# mother_card_1.net
KiCad netlist of a schematic drawn in EAGLE
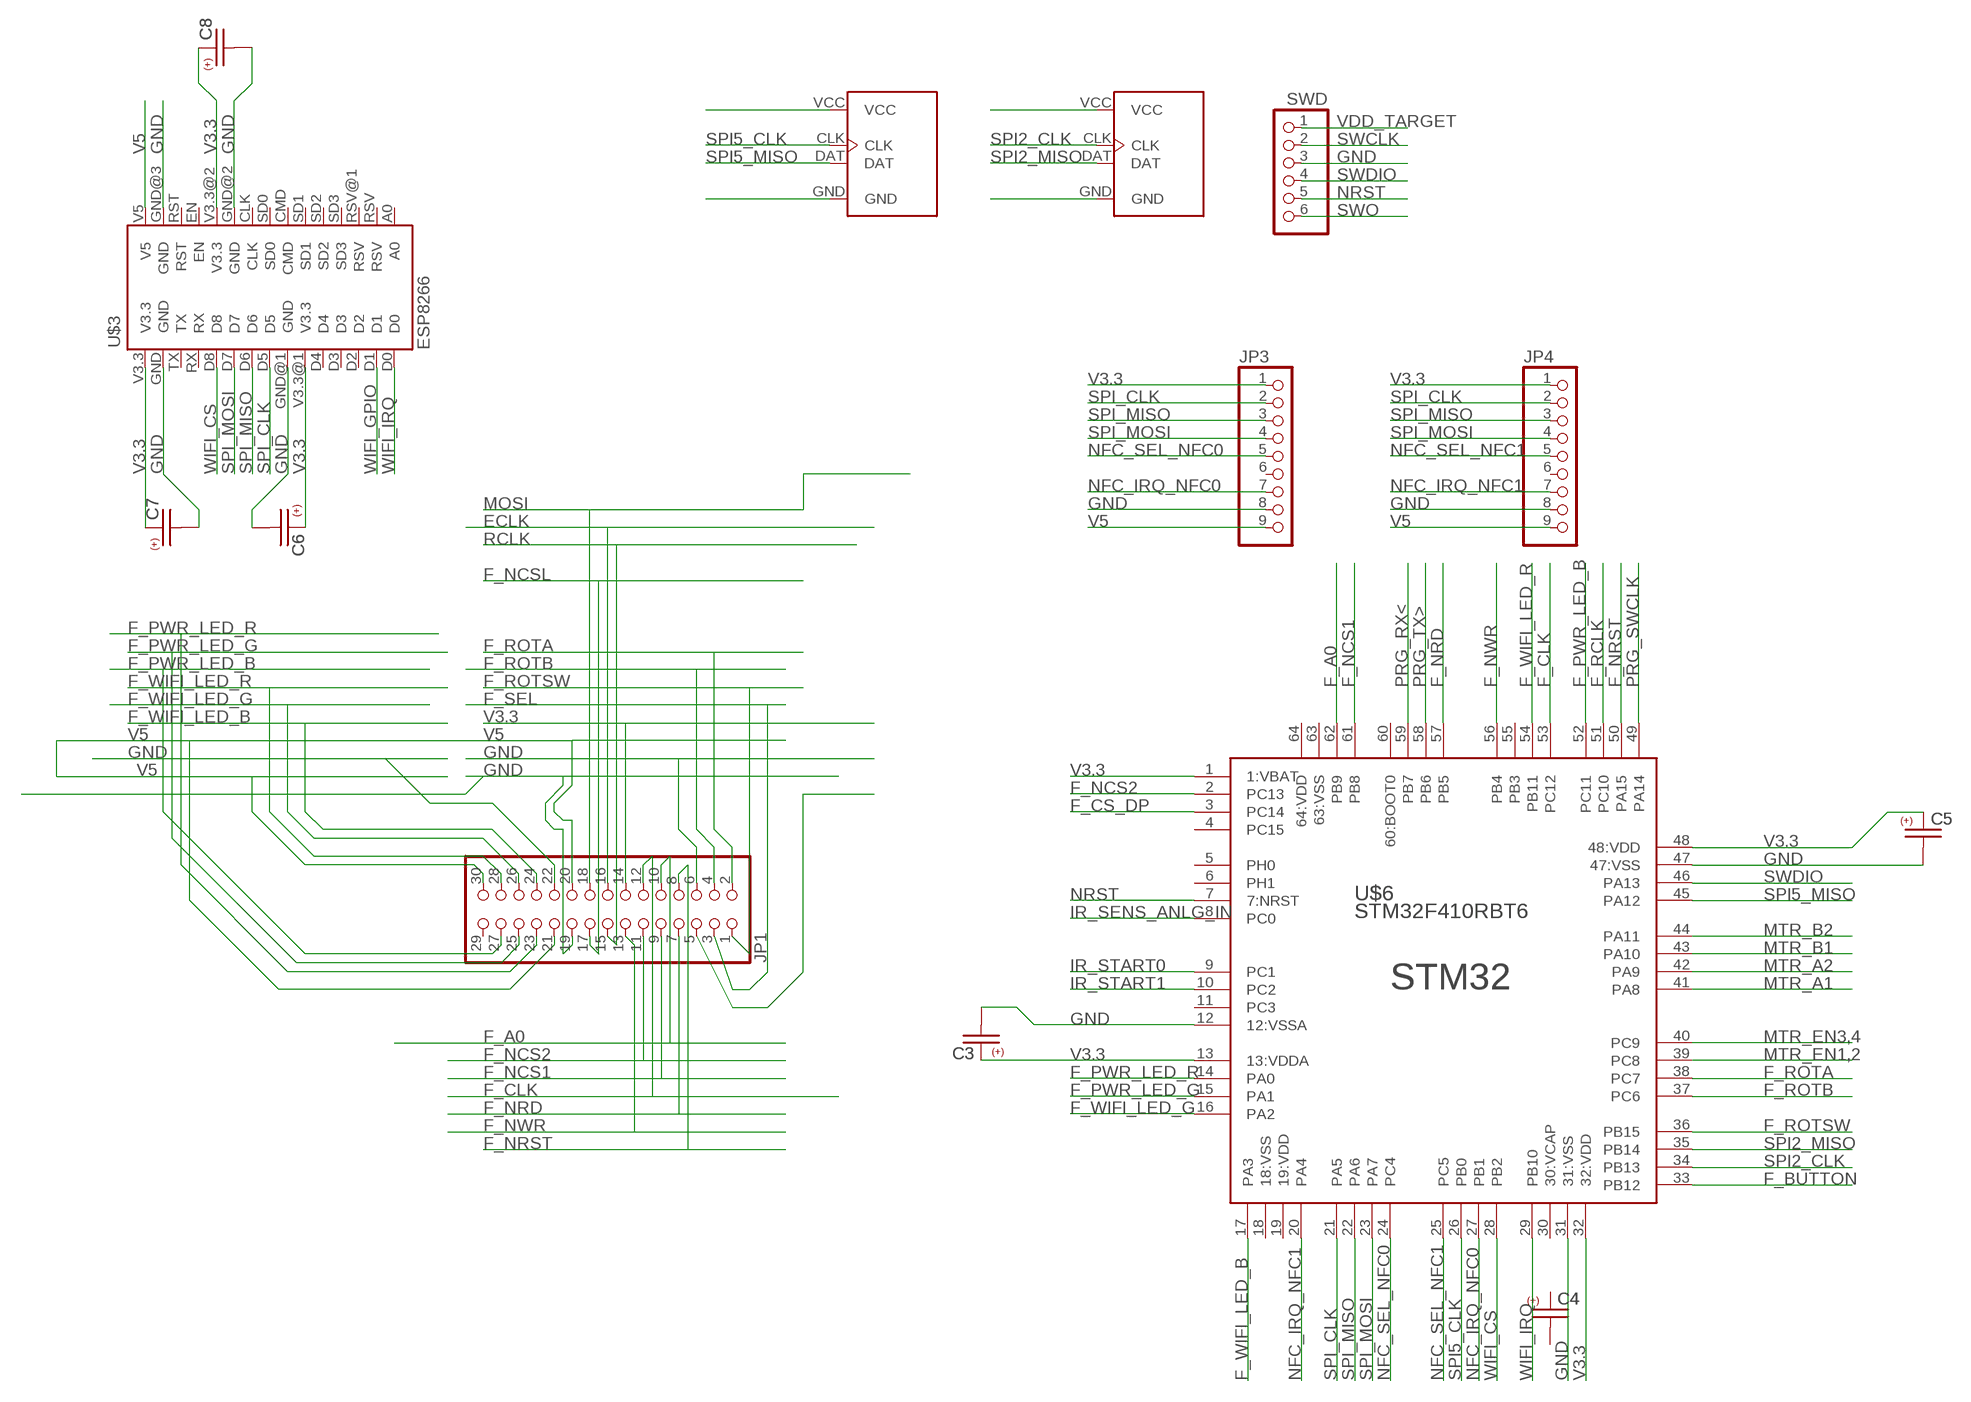
[diagram p0: schematic, sheet 1]
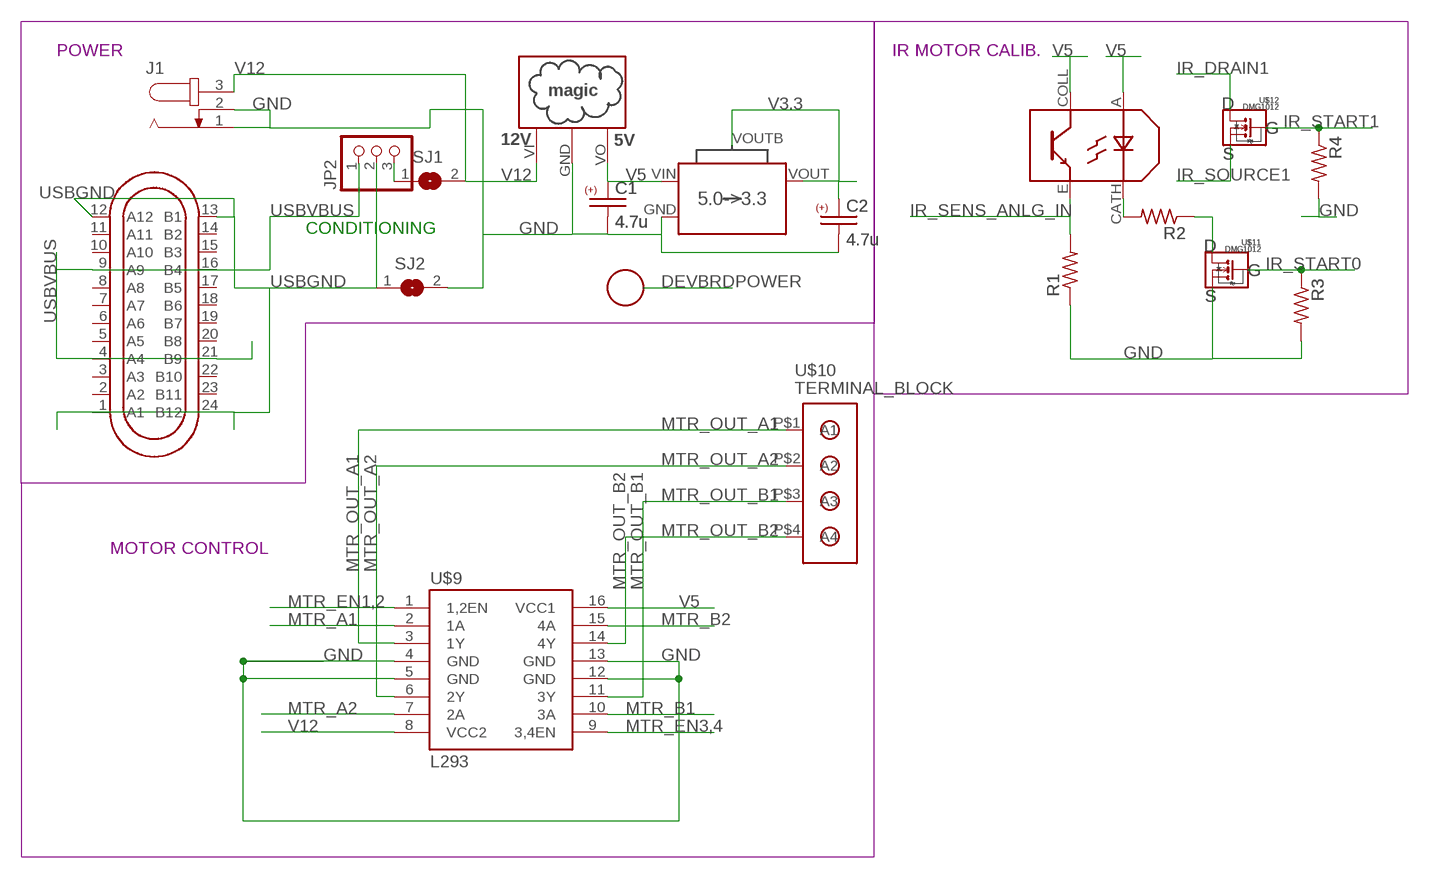
[diagram p1: schematic, sheet 2]
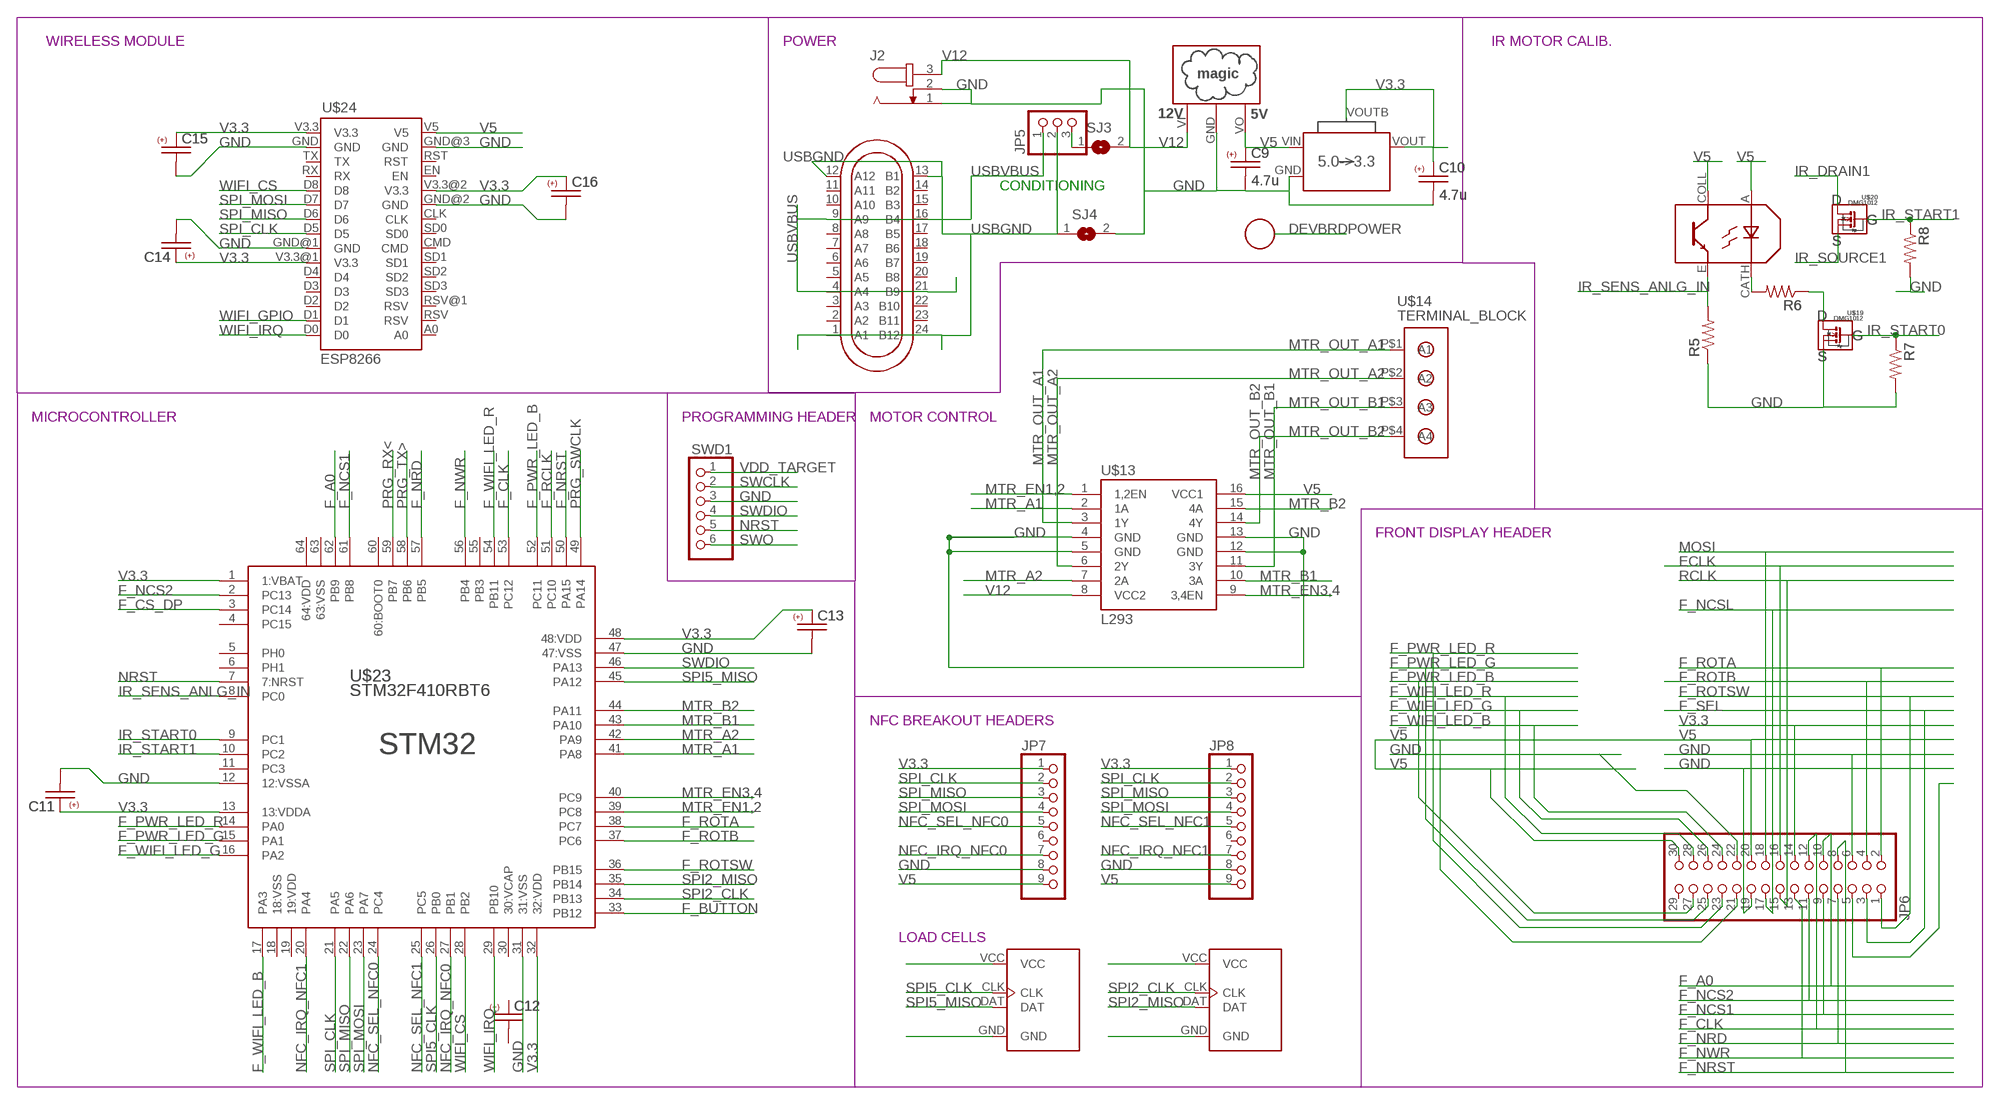
[diagram p2: schematic, sheet 3]

(export (version "E")
  (design (tool "Eeschema 10.0.6"))
  (components
    (comp (ref "C9")
      (value "4.7u")
      (footprint "eagle-import:C0805")
      (libsource (lib "eagle-import") (part "C-USC0805"))
    )
    (comp (ref "C10")
      (value "4.7u")
      (footprint "eagle-import:C0805")
      (libsource (lib "eagle-import") (part "C-USC0805"))
    )
    (comp (ref "C11")
      (value "C-USC0805")
      (footprint "eagle-import:C0805")
      (libsource (lib "eagle-import") (part "C-USC0805"))
    )
    (comp (ref "C12")
      (value "C-USC0805")
      (footprint "eagle-import:C0805")
      (libsource (lib "eagle-import") (part "C-USC0805"))
    )
    (comp (ref "C13")
      (value "C-USC0805")
      (footprint "eagle-import:C0805")
      (libsource (lib "eagle-import") (part "C-USC0805"))
    )
    (comp (ref "C14")
      (value "C-USC0805")
      (footprint "eagle-import:C0805")
      (libsource (lib "eagle-import") (part "C-USC0805"))
    )
    (comp (ref "C15")
      (value "C-USC0805")
      (footprint "eagle-import:C0805")
      (libsource (lib "eagle-import") (part "C-USC0805"))
    )
    (comp (ref "C16")
      (value "C-USC0805")
      (footprint "eagle-import:C0805")
      (libsource (lib "eagle-import") (part "C-USC0805"))
    )
    (comp (ref "J2")
      (value "JACK-PLUG0")
      (footprint "eagle-import:SPC4077")
      (libsource (lib "eagle-import") (part "JACK-PLUG0"))
    )
    (comp (ref "JP5")
      (value "PINHD-1X3")
      (footprint "eagle-import:1X03")
      (libsource (lib "eagle-import") (part "PINHD-1X3"))
    )
    (comp (ref "JP6")
      (value "PINHD-2X15/SOCK")
      (footprint "eagle-import:2X15_SOCK")
      (libsource (lib "eagle-import") (part "PINHD-2X15/SOCK"))
    )
    (comp (ref "JP7")
      (value "PINHD-1X9/90")
      (footprint "eagle-import:1X09_90")
      (libsource (lib "eagle-import") (part "PINHD-1X9/90"))
    )
    (comp (ref "JP8")
      (value "PINHD-1X9/90")
      (footprint "eagle-import:1X09_90")
      (libsource (lib "eagle-import") (part "PINHD-1X9/90"))
    )
    (comp (ref "R5")
      (value "R-US_R0805")
      (footprint "eagle-import:R0805")
      (libsource (lib "eagle-import") (part "R-US_R0805"))
    )
    (comp (ref "R6")
      (value "R-US_R0805")
      (footprint "eagle-import:R0805")
      (libsource (lib "eagle-import") (part "R-US_R0805"))
    )
    (comp (ref "R7")
      (value "R-US_R0805")
      (footprint "eagle-import:R0805")
      (libsource (lib "eagle-import") (part "R-US_R0805"))
    )
    (comp (ref "R8")
      (value "R-US_R0805")
      (footprint "eagle-import:R0805")
      (libsource (lib "eagle-import") (part "R-US_R0805"))
    )
    (comp (ref "SJ3") (value "SJ") (footprint "eagle-import:SJ") (libsource (lib "eagle-import") (part "SJ")))
    (comp (ref "SJ4") (value "SJ") (footprint "eagle-import:SJ") (libsource (lib "eagle-import") (part "SJ")))
    (comp (ref "SWD1")
      (value "PINHD-1X6")
      (footprint "eagle-import:1X06")
      (libsource (lib "eagle-import") (part "PINHD-1X6"))
    )
    (comp (ref "U$13")
      (value "L293")
      (footprint "eagle-import:DIL16")
      (libsource (lib "eagle-import") (part "L293"))
    )
    (comp (ref "U$14")
      (value "TERMINAL_BLOCK")
      (footprint "eagle-import:1X4_BLOCK")
      (libsource (lib "eagle-import") (part "TERMINAL_BLOCK"))
    )
    (comp (ref "U$15")
      (value "AP2114H")
      (footprint "eagle-import:AP2114H")
      (libsource (lib "eagle-import") (part "AP2114H"))
    )
    (comp (ref "U$16")
      (value "OKI-78SR-W36")
      (footprint "eagle-import:SIP3")
      (libsource (lib "eagle-import") (part "OKI-78SR-W36"))
    )
    (comp (ref "U$17")
      (value "USB-C-BRKOUT")
      (footprint "eagle-import:USB-C-BRKOUT")
      (libsource (lib "eagle-import") (part "USB-C-BRKOUT"))
    )
    (comp (ref "U$18")
      (value "TCRT5000")
      (footprint "eagle-import:TCRT5000")
      (libsource (lib "eagle-import") (part "TCRT5000"))
    )
    (comp (ref "U$19")
      (value "DMG1012")
      (footprint "eagle-import:SOT323")
      (libsource (lib "eagle-import") (part "DMG1012"))
    )
    (comp (ref "U$20")
      (value "DMG1012")
      (footprint "eagle-import:SOT323")
      (libsource (lib "eagle-import") (part "DMG1012"))
    )
    (comp (ref "U$21")
      (value "HX711")
      (footprint "eagle-import:HX711")
      (libsource (lib "eagle-import") (part "HX711"))
    )
    (comp (ref "U$22")
      (value "HX711")
      (footprint "eagle-import:HX711")
      (libsource (lib "eagle-import") (part "HX711"))
    )
    (comp (ref "U$23")
      (value "STM32F410RBT6")
      (footprint "eagle-import:QFP50P1200X1200X160-64N")
      (libsource (lib "eagle-import") (part "STM32F410RBT6"))
    )
    (comp (ref "U$24")
      (value "ESP8266")
      (footprint "eagle-import:ESP8266")
      (libsource (lib "eagle-import") (part "ESP8266"))
    )
    (comp (ref "C3")
      (value "C-USC0805")
      (footprint "eagle-import:C0805")
      (libsource (lib "eagle-import") (part "C-USC0805"))
    )
    (comp (ref "C4")
      (value "C-USC0805")
      (footprint "eagle-import:C0805")
      (libsource (lib "eagle-import") (part "C-USC0805"))
    )
    (comp (ref "C5")
      (value "C-USC0805")
      (footprint "eagle-import:C0805")
      (libsource (lib "eagle-import") (part "C-USC0805"))
    )
    (comp (ref "C6")
      (value "C-USC0805")
      (footprint "eagle-import:C0805")
      (libsource (lib "eagle-import") (part "C-USC0805"))
    )
    (comp (ref "C7")
      (value "C-USC0805")
      (footprint "eagle-import:C0805")
      (libsource (lib "eagle-import") (part "C-USC0805"))
    )
    (comp (ref "C8")
      (value "C-USC0805")
      (footprint "eagle-import:C0805")
      (libsource (lib "eagle-import") (part "C-USC0805"))
    )
    (comp (ref "JP1")
      (value "PINHD-2X15/SOCK")
      (footprint "eagle-import:2X15_SOCK")
      (libsource (lib "eagle-import") (part "PINHD-2X15/SOCK"))
    )
    (comp (ref "JP3")
      (value "PINHD-1X9/90")
      (footprint "eagle-import:1X09_90")
      (libsource (lib "eagle-import") (part "PINHD-1X9/90"))
    )
    (comp (ref "JP4")
      (value "PINHD-1X9/90")
      (footprint "eagle-import:1X09_90")
      (libsource (lib "eagle-import") (part "PINHD-1X9/90"))
    )
    (comp (ref "SWD")
      (value "PINHD-1X6")
      (footprint "eagle-import:1X06")
      (libsource (lib "eagle-import") (part "PINHD-1X6"))
    )
    (comp (ref "U$1")
      (value "HX711")
      (footprint "eagle-import:HX711")
      (libsource (lib "eagle-import") (part "HX711"))
    )
    (comp (ref "U$2")
      (value "HX711")
      (footprint "eagle-import:HX711")
      (libsource (lib "eagle-import") (part "HX711"))
    )
    (comp (ref "U$3")
      (value "ESP8266")
      (footprint "eagle-import:ESP8266")
      (libsource (lib "eagle-import") (part "ESP8266"))
    )
    (comp (ref "U$6")
      (value "STM32F410RBT6")
      (footprint "eagle-import:QFP50P1200X1200X160-64N")
      (libsource (lib "eagle-import") (part "STM32F410RBT6"))
    )
    (comp (ref "C1")
      (value "4.7u")
      (footprint "eagle-import:C0805")
      (libsource (lib "eagle-import") (part "C-USC0805"))
    )
    (comp (ref "C2")
      (value "4.7u")
      (footprint "eagle-import:C0805")
      (libsource (lib "eagle-import") (part "C-USC0805"))
    )
    (comp (ref "J1")
      (value "JACK-PLUG0")
      (footprint "eagle-import:SPC4077")
      (libsource (lib "eagle-import") (part "JACK-PLUG0"))
    )
    (comp (ref "JP2")
      (value "PINHD-1X3")
      (footprint "eagle-import:1X03")
      (libsource (lib "eagle-import") (part "PINHD-1X3"))
    )
    (comp (ref "R1")
      (value "R-US_R0805")
      (footprint "eagle-import:R0805")
      (libsource (lib "eagle-import") (part "R-US_R0805"))
    )
    (comp (ref "R2")
      (value "R-US_R0805")
      (footprint "eagle-import:R0805")
      (libsource (lib "eagle-import") (part "R-US_R0805"))
    )
    (comp (ref "R3")
      (value "R-US_R0805")
      (footprint "eagle-import:R0805")
      (libsource (lib "eagle-import") (part "R-US_R0805"))
    )
    (comp (ref "R4")
      (value "R-US_R0805")
      (footprint "eagle-import:R0805")
      (libsource (lib "eagle-import") (part "R-US_R0805"))
    )
    (comp (ref "SJ1") (value "SJ") (footprint "eagle-import:SJ") (libsource (lib "eagle-import") (part "SJ")))
    (comp (ref "SJ2") (value "SJ") (footprint "eagle-import:SJ") (libsource (lib "eagle-import") (part "SJ")))
    (comp (ref "U$4")
      (value "OKI-78SR-W36")
      (footprint "eagle-import:SIP3")
      (libsource (lib "eagle-import") (part "OKI-78SR-W36"))
    )
    (comp (ref "U$5")
      (value "TCRT5000")
      (footprint "eagle-import:TCRT5000")
      (libsource (lib "eagle-import") (part "TCRT5000"))
    )
    (comp (ref "U$7")
      (value "USB-C-BRKOUT")
      (footprint "eagle-import:USB-C-BRKOUT")
      (libsource (lib "eagle-import") (part "USB-C-BRKOUT"))
    )
    (comp (ref "U$8")
      (value "AP2114H")
      (footprint "eagle-import:AP2114H")
      (libsource (lib "eagle-import") (part "AP2114H"))
    )
    (comp (ref "U$9")
      (value "L293")
      (footprint "eagle-import:DIL16")
      (libsource (lib "eagle-import") (part "L293"))
    )
    (comp (ref "U$10")
      (value "TERMINAL_BLOCK")
      (footprint "eagle-import:1X4_BLOCK")
      (libsource (lib "eagle-import") (part "TERMINAL_BLOCK"))
    )
    (comp (ref "U$11")
      (value "DMG1012")
      (footprint "eagle-import:SOT323")
      (libsource (lib "eagle-import") (part "DMG1012"))
    )
    (comp (ref "U$12")
      (value "DMG1012")
      (footprint "eagle-import:SOT323")
      (libsource (lib "eagle-import") (part "DMG1012"))
    )
  )
  (nets
    (net (code "2") (name "ECLK") (class "Default")
      (node (ref "JP1") (pin "16") (pinfunction "16_16") (pintype "passive"))
      (node (ref "JP6") (pin "16") (pinfunction "16_16") (pintype "passive"))
    )
    (net (code "3") (name "F_A0") (class "Default")
      (node (ref "JP1") (pin "10") (pinfunction "10_10") (pintype "passive"))
      (node (ref "JP6") (pin "10") (pinfunction "10_10") (pintype "passive"))
      (node (ref "U$23") (pin "62") (pinfunction "PB9_62") (pintype "bidirectional"))
      (node (ref "U$6") (pin "62") (pinfunction "PB9_62") (pintype "bidirectional"))
    )
    (net (code "4") (name "F_BUTTON") (class "Default")
      (node (ref "U$23") (pin "33") (pinfunction "PB12_33") (pintype "bidirectional"))
      (node (ref "U$6") (pin "33") (pinfunction "PB12_33") (pintype "bidirectional"))
    )
    (net (code "5") (name "F_CLK") (class "Default")
      (node (ref "JP1") (pin "12") (pinfunction "12_12") (pintype "passive"))
      (node (ref "JP6") (pin "12") (pinfunction "12_12") (pintype "passive"))
      (node (ref "U$23") (pin "53") (pinfunction "PC12_53") (pintype "bidirectional"))
      (node (ref "U$6") (pin "53") (pinfunction "PC12_53") (pintype "bidirectional"))
    )
    (net (code "6") (name "F_CS_DP") (class "Default")
      (node (ref "U$23") (pin "3") (pinfunction "PC14_3") (pintype "bidirectional"))
      (node (ref "U$6") (pin "3") (pinfunction "PC14_3") (pintype "bidirectional"))
    )
    (net (code "7") (name "F_NCS1") (class "Default")
      (node (ref "JP1") (pin "9") (pinfunction "9_9") (pintype "passive"))
      (node (ref "JP6") (pin "9") (pinfunction "9_9") (pintype "passive"))
      (node (ref "U$23") (pin "61") (pinfunction "PB8_61") (pintype "bidirectional"))
      (node (ref "U$6") (pin "61") (pinfunction "PB8_61") (pintype "bidirectional"))
    )
    (net (code "8") (name "F_NCS2") (class "Default")
      (node (ref "JP1") (pin "11") (pinfunction "11_11") (pintype "passive"))
      (node (ref "JP6") (pin "11") (pinfunction "11_11") (pintype "passive"))
      (node (ref "U$23") (pin "2") (pinfunction "PC13_2") (pintype "bidirectional"))
      (node (ref "U$6") (pin "2") (pinfunction "PC13_2") (pintype "bidirectional"))
    )
    (net (code "9") (name "F_NCSL") (class "Default")
      (node (ref "JP1") (pin "17") (pinfunction "17_17") (pintype "passive"))
      (node (ref "JP6") (pin "17") (pinfunction "17_17") (pintype "passive"))
    )
    (net (code "10") (name "F_NRD") (class "Default")
      (node (ref "JP1") (pin "7") (pinfunction "7_7") (pintype "passive"))
      (node (ref "JP6") (pin "7") (pinfunction "7_7") (pintype "passive"))
      (node (ref "U$23") (pin "57") (pinfunction "PB5_57") (pintype "bidirectional"))
      (node (ref "U$6") (pin "57") (pinfunction "PB5_57") (pintype "bidirectional"))
    )
    (net (code "11") (name "F_NRST") (class "Default")
      (node (ref "JP1") (pin "8") (pinfunction "8_8") (pintype "passive"))
      (node (ref "JP6") (pin "8") (pinfunction "8_8") (pintype "passive"))
      (node (ref "U$23") (pin "50") (pinfunction "PA15_50") (pintype "bidirectional"))
      (node (ref "U$6") (pin "50") (pinfunction "PA15_50") (pintype "bidirectional"))
    )
    (net (code "12") (name "F_NWR") (class "Default")
      (node (ref "JP1") (pin "13") (pinfunction "13_13") (pintype "passive"))
      (node (ref "JP6") (pin "13") (pinfunction "13_13") (pintype "passive"))
      (node (ref "U$23") (pin "56") (pinfunction "PB4_56") (pintype "bidirectional"))
      (node (ref "U$6") (pin "56") (pinfunction "PB4_56") (pintype "bidirectional"))
    )
    (net (code "13") (name "F_PWR_LED_B") (class "Default")
      (node (ref "JP1") (pin "27") (pinfunction "27_27") (pintype "passive"))
      (node (ref "JP6") (pin "27") (pinfunction "27_27") (pintype "passive"))
      (node (ref "U$23") (pin "52") (pinfunction "PC11_52") (pintype "bidirectional"))
      (node (ref "U$6") (pin "52") (pinfunction "PC11_52") (pintype "bidirectional"))
    )
    (net (code "14") (name "F_PWR_LED_G") (class "Default")
      (node (ref "JP1") (pin "25") (pinfunction "25_25") (pintype "passive"))
      (node (ref "JP6") (pin "25") (pinfunction "25_25") (pintype "passive"))
      (node (ref "U$23") (pin "15") (pinfunction "PA1_15") (pintype "bidirectional"))
      (node (ref "U$6") (pin "15") (pinfunction "PA1_15") (pintype "bidirectional"))
    )
    (net (code "15") (name "F_PWR_LED_R") (class "Default")
      (node (ref "JP1") (pin "23") (pinfunction "23_23") (pintype "passive"))
      (node (ref "JP6") (pin "23") (pinfunction "23_23") (pintype "passive"))
      (node (ref "U$23") (pin "14") (pinfunction "PA0_14") (pintype "bidirectional"))
      (node (ref "U$6") (pin "14") (pinfunction "PA0_14") (pintype "bidirectional"))
    )
    (net (code "16") (name "F_RCLK") (class "Default")
      (node (ref "U$23") (pin "51") (pinfunction "PC10_51") (pintype "bidirectional"))
      (node (ref "U$6") (pin "51") (pinfunction "PC10_51") (pintype "bidirectional"))
    )
    (net (code "17") (name "F_ROTA") (class "Default")
      (node (ref "JP1") (pin "2") (pinfunction "2_2") (pintype "passive"))
      (node (ref "JP6") (pin "2") (pinfunction "2_2") (pintype "passive"))
      (node (ref "U$23") (pin "38") (pinfunction "PC7_38") (pintype "bidirectional"))
      (node (ref "U$6") (pin "38") (pinfunction "PC7_38") (pintype "bidirectional"))
    )
    (net (code "18") (name "F_ROTB") (class "Default")
      (node (ref "JP1") (pin "4") (pinfunction "4_4") (pintype "passive"))
      (node (ref "JP6") (pin "4") (pinfunction "4_4") (pintype "passive"))
      (node (ref "U$23") (pin "37") (pinfunction "PC6_37") (pintype "bidirectional"))
      (node (ref "U$6") (pin "37") (pinfunction "PC6_37") (pintype "bidirectional"))
    )
    (net (code "19") (name "F_ROTSW") (class "Default")
      (node (ref "JP1") (pin "1") (pinfunction "1_1") (pintype "passive"))
      (node (ref "JP6") (pin "1") (pinfunction "1_1") (pintype "passive"))
      (node (ref "U$23") (pin "36") (pinfunction "PB15_36") (pintype "bidirectional"))
      (node (ref "U$6") (pin "36") (pinfunction "PB15_36") (pintype "bidirectional"))
    )
    (net (code "20") (name "F_SEL") (class "Default")
      (node (ref "JP1") (pin "3") (pinfunction "3_3") (pintype "passive"))
      (node (ref "JP6") (pin "3") (pinfunction "3_3") (pintype "passive"))
    )
    (net (code "21") (name "F_WIFI_LED_B") (class "Default")
      (node (ref "JP1") (pin "24") (pinfunction "24_24") (pintype "passive"))
      (node (ref "JP6") (pin "24") (pinfunction "24_24") (pintype "passive"))
      (node (ref "U$23") (pin "17") (pinfunction "PA3_17") (pintype "bidirectional"))
      (node (ref "U$6") (pin "17") (pinfunction "PA3_17") (pintype "bidirectional"))
    )
    (net (code "22") (name "F_WIFI_LED_G") (class "Default")
      (node (ref "JP1") (pin "26") (pinfunction "26_26") (pintype "passive"))
      (node (ref "JP6") (pin "26") (pinfunction "26_26") (pintype "passive"))
      (node (ref "U$23") (pin "16") (pinfunction "PA2_16") (pintype "bidirectional"))
      (node (ref "U$6") (pin "16") (pinfunction "PA2_16") (pintype "bidirectional"))
    )
    (net (code "23") (name "F_WIFI_LED_R") (class "Default")
      (node (ref "JP1") (pin "28") (pinfunction "28_28") (pintype "passive"))
      (node (ref "JP6") (pin "28") (pinfunction "28_28") (pintype "passive"))
      (node (ref "U$23") (pin "54") (pinfunction "PB11_54") (pintype "bidirectional"))
      (node (ref "U$6") (pin "54") (pinfunction "PB11_54") (pintype "bidirectional"))
    )
    (net (code "24") (name "GND") (class "Default")
      (node (ref "C1") (pin "2") (pinfunction "2_2") (pintype "passive"))
      (node (ref "C10") (pin "2") (pinfunction "2_2") (pintype "passive"))
      (node (ref "C11") (pin "2") (pinfunction "2_2") (pintype "passive"))
      (node (ref "C13") (pin "2") (pinfunction "2_2") (pintype "passive"))
      (node (ref "C14") (pin "2") (pinfunction "2_2") (pintype "passive"))
      (node (ref "C15") (pin "2") (pinfunction "2_2") (pintype "passive"))
      (node (ref "C16") (pin "2") (pinfunction "2_2") (pintype "passive"))
      (node (ref "C2") (pin "2") (pinfunction "2_2") (pintype "passive"))
      (node (ref "C3") (pin "2") (pinfunction "2_2") (pintype "passive"))
      (node (ref "C5") (pin "2") (pinfunction "2_2") (pintype "passive"))
      (node (ref "C6") (pin "2") (pinfunction "2_2") (pintype "passive"))
      (node (ref "C7") (pin "2") (pinfunction "2_2") (pintype "passive"))
      (node (ref "C8") (pin "2") (pinfunction "2_2") (pintype "passive"))
      (node (ref "C9") (pin "2") (pinfunction "2_2") (pintype "passive"))
      (node (ref "J1") (pin "1") (pinfunction "1_1") (pintype "passive"))
      (node (ref "J1") (pin "2") (pinfunction "2_2") (pintype "passive"))
      (node (ref "J2") (pin "1") (pinfunction "1_1") (pintype "passive"))
      (node (ref "J2") (pin "2") (pinfunction "2_2") (pintype "passive"))
      (node (ref "JP1") (pin "19") (pinfunction "19_19") (pintype "passive"))
      (node (ref "JP1") (pin "22") (pinfunction "22_22") (pintype "passive"))
      (node (ref "JP1") (pin "6") (pinfunction "6_6") (pintype "passive"))
      (node (ref "JP3") (pin "8") (pinfunction "8_8") (pintype "passive"))
      (node (ref "JP4") (pin "8") (pinfunction "8_8") (pintype "passive"))
      (node (ref "JP6") (pin "22") (pinfunction "22_22") (pintype "passive"))
      (node (ref "JP6") (pin "6") (pinfunction "6_6") (pintype "passive"))
      (node (ref "JP7") (pin "8") (pinfunction "8_8") (pintype "passive"))
      (node (ref "JP8") (pin "8") (pinfunction "8_8") (pintype "passive"))
      (node (ref "R1") (pin "1") (pinfunction "1_1") (pintype "passive"))
      (node (ref "R3") (pin "2") (pinfunction "2_2") (pintype "passive"))
      (node (ref "R4") (pin "2") (pinfunction "2_2") (pintype "passive"))
      (node (ref "R5") (pin "1") (pinfunction "1_1") (pintype "passive"))
      (node (ref "R7") (pin "2") (pinfunction "2_2") (pintype "passive"))
      (node (ref "R8") (pin "2") (pinfunction "2_2") (pintype "passive"))
      (node (ref "SJ2") (pin "2") (pinfunction "2_2") (pintype "passive"))
      (node (ref "SJ4") (pin "2") (pinfunction "2_2") (pintype "passive"))
      (node (ref "SWD") (pin "3") (pinfunction "3_3") (pintype "passive"))
      (node (ref "SWD1") (pin "3") (pinfunction "3_3") (pintype "passive"))
      (node (ref "U$11") (pin "S") (pinfunction "S_S") (pintype "bidirectional"))
      (node (ref "U$13") (pin "12") (pinfunction "GND_12") (pintype "bidirectional"))
      (node (ref "U$13") (pin "13") (pinfunction "GND_13") (pintype "bidirectional"))
      (node (ref "U$13") (pin "4") (pinfunction "GND_4") (pintype "bidirectional"))
      (node (ref "U$13") (pin "5") (pinfunction "GND_5") (pintype "bidirectional"))
      (node (ref "U$15") (pin "GND") (pinfunction "GND_GND") (pintype "power_in"))
      (node (ref "U$16") (pin "GND") (pinfunction "P$2_GND") (pintype "power_in"))
      (node (ref "U$19") (pin "S") (pinfunction "S_S") (pintype "bidirectional"))
      (node (ref "U$23") (pin "12") (pinfunction "12:VSSA_12") (pintype "bidirectional"))
      (node (ref "U$23") (pin "31") (pinfunction "31:VSS_31") (pintype "bidirectional"))
      (node (ref "U$23") (pin "47") (pinfunction "47:VSS_47") (pintype "bidirectional"))
      (node (ref "U$24") (pin "GND") (pinfunction "GND_GND") (pintype "bidirectional"))
      (node (ref "U$24") (pin "GND@1") (pinfunction "GND_GND@1") (pintype "bidirectional"))
      (node (ref "U$24") (pin "GND@2") (pinfunction "GND_GND@2") (pintype "bidirectional"))
      (node (ref "U$24") (pin "GND@3") (pinfunction "GND_GND@3") (pintype "bidirectional"))
      (node (ref "U$3") (pin "GND") (pinfunction "GND_GND") (pintype "bidirectional"))
      (node (ref "U$3") (pin "GND@1") (pinfunction "GND_GND@1") (pintype "bidirectional"))
      (node (ref "U$3") (pin "GND@2") (pinfunction "GND_GND@2") (pintype "bidirectional"))
      (node (ref "U$3") (pin "GND@3") (pinfunction "GND_GND@3") (pintype "bidirectional"))
      (node (ref "U$4") (pin "GND") (pinfunction "P$2_GND") (pintype "power_in"))
      (node (ref "U$6") (pin "12") (pinfunction "12:VSSA_12") (pintype "bidirectional"))
      (node (ref "U$6") (pin "31") (pinfunction "31:VSS_31") (pintype "bidirectional"))
      (node (ref "U$6") (pin "47") (pinfunction "47:VSS_47") (pintype "bidirectional"))
      (node (ref "U$8") (pin "GND") (pinfunction "GND_GND") (pintype "power_in"))
      (node (ref "U$9") (pin "12") (pinfunction "GND_12") (pintype "bidirectional"))
      (node (ref "U$9") (pin "13") (pinfunction "GND_13") (pintype "bidirectional"))
      (node (ref "U$9") (pin "4") (pinfunction "GND_4") (pintype "bidirectional"))
      (node (ref "U$9") (pin "5") (pinfunction "GND_5") (pintype "bidirectional"))
    )
    (net (code "25") (name "IR_DRAIN1") (class "Default")
      (node (ref "U$12") (pin "D") (pinfunction "D_D") (pintype "bidirectional"))
      (node (ref "U$20") (pin "D") (pinfunction "D_D") (pintype "bidirectional"))
    )
    (net (code "26") (name "IR_SENS_ANLG_IN") (class "Default")
      (node (ref "R1") (pin "2") (pinfunction "2_2") (pintype "passive"))
      (node (ref "R5") (pin "2") (pinfunction "2_2") (pintype "passive"))
      (node (ref "U$18") (pin "E") (pinfunction "E_E") (pintype "bidirectional"))
      (node (ref "U$23") (pin "8") (pinfunction "PC0_8") (pintype "bidirectional"))
      (node (ref "U$5") (pin "E") (pinfunction "E_E") (pintype "bidirectional"))
      (node (ref "U$6") (pin "8") (pinfunction "PC0_8") (pintype "bidirectional"))
    )
    (net (code "27") (name "IR_SOURCE1") (class "Default")
      (node (ref "U$12") (pin "S") (pinfunction "S_S") (pintype "bidirectional"))
      (node (ref "U$20") (pin "S") (pinfunction "S_S") (pintype "bidirectional"))
    )
    (net (code "28") (name "IR_START0") (class "Default")
      (node (ref "R3") (pin "1") (pinfunction "1_1") (pintype "passive"))
      (node (ref "R7") (pin "1") (pinfunction "1_1") (pintype "passive"))
      (node (ref "U$11") (pin "G") (pinfunction "G_G") (pintype "bidirectional"))
      (node (ref "U$19") (pin "G") (pinfunction "G_G") (pintype "bidirectional"))
      (node (ref "U$23") (pin "9") (pinfunction "PC1_9") (pintype "bidirectional"))
      (node (ref "U$6") (pin "9") (pinfunction "PC1_9") (pintype "bidirectional"))
    )
    (net (code "29") (name "IR_START1") (class "Default")
      (node (ref "R4") (pin "1") (pinfunction "1_1") (pintype "passive"))
      (node (ref "R8") (pin "1") (pinfunction "1_1") (pintype "passive"))
      (node (ref "U$12") (pin "G") (pinfunction "G_G") (pintype "bidirectional"))
      (node (ref "U$20") (pin "G") (pinfunction "G_G") (pintype "bidirectional"))
      (node (ref "U$23") (pin "10") (pinfunction "PC2_10") (pintype "bidirectional"))
      (node (ref "U$6") (pin "10") (pinfunction "PC2_10") (pintype "bidirectional"))
    )
    (net (code "30") (name "MOSI") (class "Default")
      (node (ref "JP1") (pin "18") (pinfunction "18_18") (pintype "passive"))
      (node (ref "JP6") (pin "18") (pinfunction "18_18") (pintype "passive"))
    )
    (net (code "31") (name "MTR_A1") (class "Default")
      (node (ref "U$13") (pin "2") (pinfunction "1A_2") (pintype "bidirectional"))
      (node (ref "U$23") (pin "41") (pinfunction "PA8_41") (pintype "bidirectional"))
      (node (ref "U$6") (pin "41") (pinfunction "PA8_41") (pintype "bidirectional"))
      (node (ref "U$9") (pin "2") (pinfunction "1A_2") (pintype "bidirectional"))
    )
    (net (code "32") (name "MTR_A2") (class "Default")
      (node (ref "U$13") (pin "7") (pinfunction "2A_7") (pintype "bidirectional"))
      (node (ref "U$23") (pin "42") (pinfunction "PA9_42") (pintype "bidirectional"))
      (node (ref "U$6") (pin "42") (pinfunction "PA9_42") (pintype "bidirectional"))
      (node (ref "U$9") (pin "7") (pinfunction "2A_7") (pintype "bidirectional"))
    )
    (net (code "33") (name "MTR_B1") (class "Default")
      (node (ref "U$13") (pin "10") (pinfunction "3A_10") (pintype "bidirectional"))
      (node (ref "U$23") (pin "43") (pinfunction "PA10_43") (pintype "bidirectional"))
      (node (ref "U$6") (pin "43") (pinfunction "PA10_43") (pintype "bidirectional"))
      (node (ref "U$9") (pin "10") (pinfunction "3A_10") (pintype "bidirectional"))
    )
    (net (code "34") (name "MTR_B2") (class "Default")
      (node (ref "U$13") (pin "15") (pinfunction "4A_15") (pintype "bidirectional"))
      (node (ref "U$23") (pin "44") (pinfunction "PA11_44") (pintype "bidirectional"))
      (node (ref "U$6") (pin "44") (pinfunction "PA11_44") (pintype "bidirectional"))
      (node (ref "U$9") (pin "15") (pinfunction "4A_15") (pintype "bidirectional"))
    )
    (net (code "35") (name "MTR_EN1,2") (class "Default")
      (node (ref "U$13") (pin "1") (pinfunction "1,2EN_1") (pintype "bidirectional"))
      (node (ref "U$23") (pin "39") (pinfunction "PC8_39") (pintype "bidirectional"))
      (node (ref "U$6") (pin "39") (pinfunction "PC8_39") (pintype "bidirectional"))
      (node (ref "U$9") (pin "1") (pinfunction "1,2EN_1") (pintype "bidirectional"))
    )
    (net (code "36") (name "MTR_EN3,4") (class "Default")
      (node (ref "U$13") (pin "9") (pinfunction "3,4EN_9") (pintype "bidirectional"))
      (node (ref "U$23") (pin "40") (pinfunction "PC9_40") (pintype "bidirectional"))
      (node (ref "U$6") (pin "40") (pinfunction "PC9_40") (pintype "bidirectional"))
      (node (ref "U$9") (pin "9") (pinfunction "3,4EN_9") (pintype "bidirectional"))
    )
    (net (code "37") (name "MTR_OUT_A1") (class "Default")
      (node (ref "U$10") (pin "P$1") (pinfunction "A1_P$1") (pintype "bidirectional"))
      (node (ref "U$13") (pin "3") (pinfunction "1Y_3") (pintype "bidirectional"))
      (node (ref "U$14") (pin "P$1") (pinfunction "A1_P$1") (pintype "bidirectional"))
      (node (ref "U$9") (pin "3") (pinfunction "1Y_3") (pintype "bidirectional"))
    )
    (net (code "38") (name "MTR_OUT_A2") (class "Default")
      (node (ref "U$10") (pin "P$2") (pinfunction "A2_P$2") (pintype "bidirectional"))
      (node (ref "U$13") (pin "6") (pinfunction "2Y_6") (pintype "bidirectional"))
      (node (ref "U$14") (pin "P$2") (pinfunction "A2_P$2") (pintype "bidirectional"))
      (node (ref "U$9") (pin "6") (pinfunction "2Y_6") (pintype "bidirectional"))
    )
    (net (code "39") (name "MTR_OUT_B1") (class "Default")
      (node (ref "U$10") (pin "P$3") (pinfunction "A3_P$3") (pintype "bidirectional"))
      (node (ref "U$13") (pin "11") (pinfunction "3Y_11") (pintype "bidirectional"))
      (node (ref "U$14") (pin "P$3") (pinfunction "A3_P$3") (pintype "bidirectional"))
      (node (ref "U$9") (pin "11") (pinfunction "3Y_11") (pintype "bidirectional"))
    )
    (net (code "40") (name "MTR_OUT_B2") (class "Default")
      (node (ref "U$10") (pin "P$4") (pinfunction "A4_P$4") (pintype "bidirectional"))
      (node (ref "U$13") (pin "14") (pinfunction "4Y_14") (pintype "bidirectional"))
      (node (ref "U$14") (pin "P$4") (pinfunction "A4_P$4") (pintype "bidirectional"))
      (node (ref "U$9") (pin "14") (pinfunction "4Y_14") (pintype "bidirectional"))
    )
    (net (code "41") (name "NFC_IRQ_NFC0") (class "Default")
      (node (ref "JP3") (pin "7") (pinfunction "7_7") (pintype "passive"))
      (node (ref "JP7") (pin "7") (pinfunction "7_7") (pintype "passive"))
      (node (ref "U$23") (pin "27") (pinfunction "PB1_27") (pintype "bidirectional"))
      (node (ref "U$6") (pin "27") (pinfunction "PB1_27") (pintype "bidirectional"))
    )
    (net (code "42") (name "NFC_IRQ_NFC1") (class "Default")
      (node (ref "JP4") (pin "7") (pinfunction "7_7") (pintype "passive"))
      (node (ref "JP8") (pin "7") (pinfunction "7_7") (pintype "passive"))
      (node (ref "U$23") (pin "20") (pinfunction "PA4_20") (pintype "bidirectional"))
      (node (ref "U$6") (pin "20") (pinfunction "PA4_20") (pintype "bidirectional"))
    )
    (net (code "43") (name "NFC_SEL_NFC0") (class "Default")
      (node (ref "JP3") (pin "5") (pinfunction "5_5") (pintype "passive"))
      (node (ref "JP7") (pin "5") (pinfunction "5_5") (pintype "passive"))
      (node (ref "U$23") (pin "24") (pinfunction "PC4_24") (pintype "bidirectional"))
      (node (ref "U$6") (pin "24") (pinfunction "PC4_24") (pintype "bidirectional"))
    )
    (net (code "44") (name "NFC_SEL_NFC1") (class "Default")
      (node (ref "JP4") (pin "5") (pinfunction "5_5") (pintype "passive"))
      (node (ref "JP8") (pin "5") (pinfunction "5_5") (pintype "passive"))
      (node (ref "U$23") (pin "25") (pinfunction "PC5_25") (pintype "bidirectional"))
      (node (ref "U$6") (pin "25") (pinfunction "PC5_25") (pintype "bidirectional"))
    )
    (net (code "45") (name "NRST") (class "Default")
      (node (ref "SWD") (pin "5") (pinfunction "5_5") (pintype "passive"))
      (node (ref "SWD1") (pin "5") (pinfunction "5_5") (pintype "passive"))
      (node (ref "U$23") (pin "7") (pinfunction "7:NRST_7") (pintype "bidirectional"))
      (node (ref "U$6") (pin "7") (pinfunction "7:NRST_7") (pintype "bidirectional"))
    )
    (net (code "46") (name "Net-(JP2-Pad3)") (class "Default")
      (node (ref "JP2") (pin "3") (pinfunction "3_3") (pintype "passive"))
      (node (ref "SJ1") (pin "1") (pinfunction "1_1") (pintype "passive"))
    )
    (net (code "47") (name "Net-(JP5-Pad3)") (class "Default")
      (node (ref "JP5") (pin "3") (pinfunction "3_3") (pintype "passive"))
      (node (ref "SJ3") (pin "1") (pinfunction "1_1") (pintype "passive"))
    )
    (net (code "48") (name "Net-(R2-Pad1)") (class "Default")
      (node (ref "R2") (pin "1") (pinfunction "1_1") (pintype "passive"))
      (node (ref "U$11") (pin "D") (pinfunction "D_D") (pintype "bidirectional"))
    )
    (net (code "49") (name "Net-(R2-Pad2)") (class "Default")
      (node (ref "R2") (pin "2") (pinfunction "2_2") (pintype "passive"))
      (node (ref "U$5") (pin "CATH") (pinfunction "CATH_CATH") (pintype "bidirectional"))
    )
    (net (code "50") (name "Net-(R6-Pad1)") (class "Default")
      (node (ref "R6") (pin "1") (pinfunction "1_1") (pintype "passive"))
      (node (ref "U$19") (pin "D") (pinfunction "D_D") (pintype "bidirectional"))
    )
    (net (code "51") (name "Net-(R6-Pad2)") (class "Default")
      (node (ref "R6") (pin "2") (pinfunction "2_2") (pintype "passive"))
      (node (ref "U$18") (pin "CATH") (pinfunction "CATH_CATH") (pintype "bidirectional"))
    )
    (net (code "52") (name "PRG_RX<") (class "Default")
      (node (ref "U$23") (pin "59") (pinfunction "PB7_59") (pintype "bidirectional"))
      (node (ref "U$6") (pin "59") (pinfunction "PB7_59") (pintype "bidirectional"))
    )
    (net (code "53") (name "PRG_SWCLK") (class "Default")
      (node (ref "U$23") (pin "49") (pinfunction "PA14_49") (pintype "bidirectional"))
      (node (ref "U$6") (pin "49") (pinfunction "PA14_49") (pintype "bidirectional"))
    )
    (net (code "54") (name "PRG_TX>") (class "Default")
      (node (ref "U$23") (pin "58") (pinfunction "PB6_58") (pintype "bidirectional"))
      (node (ref "U$6") (pin "58") (pinfunction "PB6_58") (pintype "bidirectional"))
    )
    (net (code "55") (name "RCLK") (class "Default")
      (node (ref "JP1") (pin "15") (pinfunction "15_15") (pintype "passive"))
      (node (ref "JP6") (pin "15") (pinfunction "15_15") (pintype "passive"))
    )
    (net (code "56") (name "SPI2_CLK") (class "Default")
      (node (ref "U$2") (pin "CLK") (pinfunction "CLK_CLK") (pintype "bidirectional"))
      (node (ref "U$22") (pin "CLK") (pinfunction "CLK_CLK") (pintype "bidirectional"))
      (node (ref "U$23") (pin "34") (pinfunction "PB13_34") (pintype "bidirectional"))
      (node (ref "U$6") (pin "34") (pinfunction "PB13_34") (pintype "bidirectional"))
    )
    (net (code "57") (name "SPI2_MISO") (class "Default")
      (node (ref "U$2") (pin "DAT") (pinfunction "DAT_DAT") (pintype "bidirectional"))
      (node (ref "U$22") (pin "DAT") (pinfunction "DAT_DAT") (pintype "bidirectional"))
      (node (ref "U$23") (pin "35") (pinfunction "PB14_35") (pintype "bidirectional"))
      (node (ref "U$6") (pin "35") (pinfunction "PB14_35") (pintype "bidirectional"))
    )
    (net (code "58") (name "SPI5_CLK") (class "Default")
      (node (ref "U$1") (pin "CLK") (pinfunction "CLK_CLK") (pintype "bidirectional"))
      (node (ref "U$21") (pin "CLK") (pinfunction "CLK_CLK") (pintype "bidirectional"))
      (node (ref "U$23") (pin "26") (pinfunction "PB0_26") (pintype "bidirectional"))
      (node (ref "U$6") (pin "26") (pinfunction "PB0_26") (pintype "bidirectional"))
    )
    (net (code "59") (name "SPI5_MISO") (class "Default")
      (node (ref "U$1") (pin "DAT") (pinfunction "DAT_DAT") (pintype "bidirectional"))
      (node (ref "U$21") (pin "DAT") (pinfunction "DAT_DAT") (pintype "bidirectional"))
      (node (ref "U$23") (pin "45") (pinfunction "PA12_45") (pintype "bidirectional"))
      (node (ref "U$6") (pin "45") (pinfunction "PA12_45") (pintype "bidirectional"))
    )
    (net (code "60") (name "SPI_CLK") (class "Default")
      (node (ref "JP3") (pin "2") (pinfunction "2_2") (pintype "passive"))
      (node (ref "JP4") (pin "2") (pinfunction "2_2") (pintype "passive"))
      (node (ref "JP7") (pin "2") (pinfunction "2_2") (pintype "passive"))
      (node (ref "JP8") (pin "2") (pinfunction "2_2") (pintype "passive"))
      (node (ref "U$23") (pin "21") (pinfunction "PA5_21") (pintype "bidirectional"))
      (node (ref "U$24") (pin "D5") (pinfunction "D5_D5") (pintype "bidirectional"))
      (node (ref "U$3") (pin "D5") (pinfunction "D5_D5") (pintype "bidirectional"))
      (node (ref "U$6") (pin "21") (pinfunction "PA5_21") (pintype "bidirectional"))
    )
    (net (code "61") (name "SPI_MISO") (class "Default")
      (node (ref "JP3") (pin "3") (pinfunction "3_3") (pintype "passive"))
      (node (ref "JP4") (pin "3") (pinfunction "3_3") (pintype "passive"))
      (node (ref "JP7") (pin "3") (pinfunction "3_3") (pintype "passive"))
      (node (ref "JP8") (pin "3") (pinfunction "3_3") (pintype "passive"))
      (node (ref "U$23") (pin "22") (pinfunction "PA6_22") (pintype "bidirectional"))
      (node (ref "U$24") (pin "D6") (pinfunction "D6_D6") (pintype "bidirectional"))
      (node (ref "U$3") (pin "D6") (pinfunction "D6_D6") (pintype "bidirectional"))
      (node (ref "U$6") (pin "22") (pinfunction "PA6_22") (pintype "bidirectional"))
    )
    (net (code "62") (name "SPI_MOSI") (class "Default")
      (node (ref "JP3") (pin "4") (pinfunction "4_4") (pintype "passive"))
      (node (ref "JP4") (pin "4") (pinfunction "4_4") (pintype "passive"))
      (node (ref "JP7") (pin "4") (pinfunction "4_4") (pintype "passive"))
      (node (ref "JP8") (pin "4") (pinfunction "4_4") (pintype "passive"))
      (node (ref "U$23") (pin "23") (pinfunction "PA7_23") (pintype "bidirectional"))
      (node (ref "U$24") (pin "D7") (pinfunction "D7_D7") (pintype "bidirectional"))
      (node (ref "U$3") (pin "D7") (pinfunction "D7_D7") (pintype "bidirectional"))
      (node (ref "U$6") (pin "23") (pinfunction "PA7_23") (pintype "bidirectional"))
    )
    (net (code "63") (name "SWCLK") (class "Default")
      (node (ref "SWD") (pin "2") (pinfunction "2_2") (pintype "passive"))
      (node (ref "SWD1") (pin "2") (pinfunction "2_2") (pintype "passive"))
    )
    (net (code "64") (name "SWDIO") (class "Default")
      (node (ref "SWD") (pin "4") (pinfunction "4_4") (pintype "passive"))
      (node (ref "SWD1") (pin "4") (pinfunction "4_4") (pintype "passive"))
      (node (ref "U$23") (pin "46") (pinfunction "PA13_46") (pintype "bidirectional"))
      (node (ref "U$6") (pin "46") (pinfunction "PA13_46") (pintype "bidirectional"))
    )
    (net (code "65") (name "SWO") (class "Default")
      (node (ref "SWD") (pin "6") (pinfunction "6_6") (pintype "passive"))
      (node (ref "SWD1") (pin "6") (pinfunction "6_6") (pintype "passive"))
    )
    (net (code "66") (name "USBGND") (class "Default")
      (node (ref "JP2") (pin "2") (pinfunction "2_2") (pintype "passive"))
      (node (ref "JP5") (pin "2") (pinfunction "2_2") (pintype "passive"))
      (node (ref "SJ2") (pin "1") (pinfunction "1_1") (pintype "passive"))
      (node (ref "SJ4") (pin "1") (pinfunction "1_1") (pintype "passive"))
      (node (ref "U$17") (pin "1") (pinfunction "A1_1") (pintype "bidirectional"))
      (node (ref "U$17") (pin "12") (pinfunction "A12_12") (pintype "bidirectional"))
      (node (ref "U$17") (pin "13") (pinfunction "B1_13") (pintype "bidirectional"))
      (node (ref "U$17") (pin "24") (pinfunction "B12_24") (pintype "bidirectional"))
      (node (ref "U$7") (pin "1") (pinfunction "A1_1") (pintype "bidirectional"))
      (node (ref "U$7") (pin "12") (pinfunction "A12_12") (pintype "bidirectional"))
      (node (ref "U$7") (pin "13") (pinfunction "B1_13") (pintype "bidirectional"))
      (node (ref "U$7") (pin "24") (pinfunction "B12_24") (pintype "bidirectional"))
    )
    (net (code "67") (name "USBVBUS") (class "Default")
      (node (ref "JP2") (pin "1") (pinfunction "1_1") (pintype "passive"))
      (node (ref "JP5") (pin "1") (pinfunction "1_1") (pintype "passive"))
      (node (ref "U$17") (pin "16") (pinfunction "B4_16") (pintype "bidirectional"))
      (node (ref "U$17") (pin "21") (pinfunction "B9_21") (pintype "bidirectional"))
      (node (ref "U$17") (pin "4") (pinfunction "A4_4") (pintype "bidirectional"))
      (node (ref "U$17") (pin "9") (pinfunction "A9_9") (pintype "bidirectional"))
      (node (ref "U$7") (pin "16") (pinfunction "B4_16") (pintype "bidirectional"))
      (node (ref "U$7") (pin "21") (pinfunction "B9_21") (pintype "bidirectional"))
      (node (ref "U$7") (pin "4") (pinfunction "A4_4") (pintype "bidirectional"))
      (node (ref "U$7") (pin "9") (pinfunction "A9_9") (pintype "bidirectional"))
    )
    (net (code "68") (name "V3.3") (class "Default")
      (node (ref "C10") (pin "1") (pinfunction "1_1") (pintype "passive"))
      (node (ref "C11") (pin "1") (pinfunction "1_1") (pintype "passive"))
      (node (ref "C13") (pin "1") (pinfunction "1_1") (pintype "passive"))
      (node (ref "C14") (pin "1") (pinfunction "1_1") (pintype "passive"))
      (node (ref "C15") (pin "1") (pinfunction "1_1") (pintype "passive"))
      (node (ref "C16") (pin "1") (pinfunction "1_1") (pintype "passive"))
      (node (ref "C2") (pin "1") (pinfunction "1_1") (pintype "passive"))
      (node (ref "C3") (pin "1") (pinfunction "1_1") (pintype "passive"))
      (node (ref "C5") (pin "1") (pinfunction "1_1") (pintype "passive"))
      (node (ref "C6") (pin "1") (pinfunction "1_1") (pintype "passive"))
      (node (ref "C7") (pin "1") (pinfunction "1_1") (pintype "passive"))
      (node (ref "C8") (pin "1") (pinfunction "1_1") (pintype "passive"))
      (node (ref "JP1") (pin "14") (pinfunction "14_14") (pintype "passive"))
      (node (ref "JP3") (pin "1") (pinfunction "1_1") (pintype "passive"))
      (node (ref "JP4") (pin "1") (pinfunction "1_1") (pintype "passive"))
      (node (ref "JP6") (pin "14") (pinfunction "14_14") (pintype "passive"))
      (node (ref "JP7") (pin "1") (pinfunction "1_1") (pintype "passive"))
      (node (ref "JP8") (pin "1") (pinfunction "1_1") (pintype "passive"))
      (node (ref "U$15") (pin "VOUT") (pinfunction "VO_VOUT") (pintype "output"))
      (node (ref "U$15") (pin "VOUTB") (pinfunction "BODY_VOUTB") (pintype "open_collector"))
      (node (ref "U$23") (pin "1") (pinfunction "1:VBAT_1") (pintype "bidirectional"))
      (node (ref "U$23") (pin "13") (pinfunction "13:VDDA_13") (pintype "bidirectional"))
      (node (ref "U$23") (pin "32") (pinfunction "32:VDD_32") (pintype "bidirectional"))
      (node (ref "U$23") (pin "48") (pinfunction "48:VDD_48") (pintype "bidirectional"))
      (node (ref "U$24") (pin "V3.3") (pinfunction "V3.3_V3.3") (pintype "bidirectional"))
      (node (ref "U$24") (pin "V3.3@1") (pinfunction "V3.3_V3.3@1") (pintype "bidirectional"))
      (node (ref "U$24") (pin "V3.3@2") (pinfunction "V3.3_V3.3@2") (pintype "bidirectional"))
      (node (ref "U$3") (pin "V3.3") (pinfunction "V3.3_V3.3") (pintype "bidirectional"))
      (node (ref "U$3") (pin "V3.3@1") (pinfunction "V3.3_V3.3@1") (pintype "bidirectional"))
      (node (ref "U$3") (pin "V3.3@2") (pinfunction "V3.3_V3.3@2") (pintype "bidirectional"))
      (node (ref "U$6") (pin "1") (pinfunction "1:VBAT_1") (pintype "bidirectional"))
      (node (ref "U$6") (pin "13") (pinfunction "13:VDDA_13") (pintype "bidirectional"))
      (node (ref "U$6") (pin "32") (pinfunction "32:VDD_32") (pintype "bidirectional"))
      (node (ref "U$6") (pin "48") (pinfunction "48:VDD_48") (pintype "bidirectional"))
      (node (ref "U$8") (pin "VOUT") (pinfunction "VO_VOUT") (pintype "output"))
      (node (ref "U$8") (pin "VOUTB") (pinfunction "BODY_VOUTB") (pintype "open_collector"))
    )
    (net (code "69") (name "V5") (class "Default")
      (node (ref "C1") (pin "1") (pinfunction "1_1") (pintype "passive"))
      (node (ref "C9") (pin "1") (pinfunction "1_1") (pintype "passive"))
      (node (ref "JP1") (pin "20") (pinfunction "20_20") (pintype "passive"))
      (node (ref "JP1") (pin "21") (pinfunction "21_21") (pintype "passive"))
      (node (ref "JP1") (pin "30") (pinfunction "30_30") (pintype "passive"))
      (node (ref "JP3") (pin "9") (pinfunction "9_9") (pintype "passive"))
      (node (ref "JP4") (pin "9") (pinfunction "9_9") (pintype "passive"))
      (node (ref "JP6") (pin "20") (pinfunction "20_20") (pintype "passive"))
      (node (ref "JP6") (pin "21") (pinfunction "21_21") (pintype "passive"))
      (node (ref "JP6") (pin "30") (pinfunction "30_30") (pintype "passive"))
      (node (ref "JP7") (pin "9") (pinfunction "9_9") (pintype "passive"))
      (node (ref "JP8") (pin "9") (pinfunction "9_9") (pintype "passive"))
      (node (ref "U$13") (pin "16") (pinfunction "VCC1_16") (pintype "bidirectional"))
      (node (ref "U$15") (pin "VIN") (pinfunction "VI_VIN") (pintype "input"))
      (node (ref "U$16") (pin "VO") (pinfunction "P$3_VO") (pintype "output"))
      (node (ref "U$18") (pin "A") (pinfunction "A_A") (pintype "bidirectional"))
      (node (ref "U$18") (pin "COLL") (pinfunction "COLL_COLL") (pintype "bidirectional"))
      (node (ref "U$24") (pin "V5") (pinfunction "V5_V5") (pintype "bidirectional"))
      (node (ref "U$3") (pin "V5") (pinfunction "V5_V5") (pintype "bidirectional"))
      (node (ref "U$4") (pin "VO") (pinfunction "P$3_VO") (pintype "output"))
      (node (ref "U$5") (pin "A") (pinfunction "A_A") (pintype "bidirectional"))
      (node (ref "U$5") (pin "COLL") (pinfunction "COLL_COLL") (pintype "bidirectional"))
      (node (ref "U$8") (pin "VIN") (pinfunction "VI_VIN") (pintype "input"))
      (node (ref "U$9") (pin "16") (pinfunction "VCC1_16") (pintype "bidirectional"))
    )
    (net (code "70") (name "V12") (class "Default")
      (node (ref "J1") (pin "3") (pinfunction "3_3") (pintype "passive"))
      (node (ref "J2") (pin "3") (pinfunction "3_3") (pintype "passive"))
      (node (ref "SJ1") (pin "2") (pinfunction "2_2") (pintype "passive"))
      (node (ref "SJ3") (pin "2") (pinfunction "2_2") (pintype "passive"))
      (node (ref "U$13") (pin "8") (pinfunction "VCC2_8") (pintype "bidirectional"))
      (node (ref "U$16") (pin "VI") (pinfunction "P$1_VI") (pintype "input"))
      (node (ref "U$4") (pin "VI") (pinfunction "P$1_VI") (pintype "input"))
      (node (ref "U$9") (pin "8") (pinfunction "VCC2_8") (pintype "bidirectional"))
    )
    (net (code "71") (name "VDD_TARGET") (class "Default")
      (node (ref "SWD") (pin "1") (pinfunction "1_1") (pintype "passive"))
      (node (ref "SWD1") (pin "1") (pinfunction "1_1") (pintype "passive"))
    )
    (net (code "72") (name "WIFI_CS") (class "Default")
      (node (ref "U$23") (pin "28") (pinfunction "PB2_28") (pintype "bidirectional"))
      (node (ref "U$24") (pin "D8") (pinfunction "D8_D8") (pintype "bidirectional"))
      (node (ref "U$3") (pin "D8") (pinfunction "D8_D8") (pintype "bidirectional"))
      (node (ref "U$6") (pin "28") (pinfunction "PB2_28") (pintype "bidirectional"))
    )
    (net (code "73") (name "WIFI_GPIO") (class "Default")
      (node (ref "U$24") (pin "D1") (pinfunction "D1_D1") (pintype "bidirectional"))
      (node (ref "U$3") (pin "D1") (pinfunction "D1_D1") (pintype "bidirectional"))
    )
    (net (code "74") (name "WIFI_IRQ") (class "Default")
      (node (ref "U$23") (pin "29") (pinfunction "PB10_29") (pintype "bidirectional"))
      (node (ref "U$24") (pin "D0") (pinfunction "D0_D0") (pintype "bidirectional"))
      (node (ref "U$3") (pin "D0") (pinfunction "D0_D0") (pintype "bidirectional"))
      (node (ref "U$6") (pin "29") (pinfunction "PB10_29") (pintype "bidirectional"))
    )
    (net (code "75") (name "unconnected-(C4-Pad1)") (class "Default")
      (node (ref "C4") (pin "1") (pinfunction "1_1") (pintype "passive"))
    )
    (net (code "76") (name "unconnected-(C4-Pad2)") (class "Default")
      (node (ref "C4") (pin "2") (pinfunction "2_2") (pintype "passive"))
    )
    (net (code "77") (name "unconnected-(C12-Pad1)") (class "Default")
      (node (ref "C12") (pin "1") (pinfunction "1_1") (pintype "passive"))
    )
    (net (code "78") (name "unconnected-(C12-Pad2)") (class "Default")
      (node (ref "C12") (pin "2") (pinfunction "2_2") (pintype "passive"))
    )
    (net (code "79") (name "unconnected-(JP1-Pad5)") (class "Default")
      (node (ref "JP1") (pin "5") (pinfunction "5_5") (pintype "passive"))
    )
    (net (code "80") (name "unconnected-(JP1-Pad29)") (class "Default")
      (node (ref "JP1") (pin "29") (pinfunction "29_29") (pintype "passive"))
    )
    (net (code "81") (name "unconnected-(JP3-Pad6)") (class "Default")
      (node (ref "JP3") (pin "6") (pinfunction "6_6") (pintype "passive"))
    )
    (net (code "82") (name "unconnected-(JP4-Pad6)") (class "Default")
      (node (ref "JP4") (pin "6") (pinfunction "6_6") (pintype "passive"))
    )
    (net (code "83") (name "unconnected-(JP6-Pad5)") (class "Default")
      (node (ref "JP6") (pin "5") (pinfunction "5_5") (pintype "passive"))
    )
    (net (code "84") (name "unconnected-(JP6-Pad19)") (class "Default")
      (node (ref "JP6") (pin "19") (pinfunction "19_19") (pintype "passive"))
    )
    (net (code "85") (name "unconnected-(JP6-Pad29)") (class "Default")
      (node (ref "JP6") (pin "29") (pinfunction "29_29") (pintype "passive"))
    )
    (net (code "86") (name "unconnected-(JP7-Pad6)") (class "Default")
      (node (ref "JP7") (pin "6") (pinfunction "6_6") (pintype "passive"))
    )
    (net (code "87") (name "unconnected-(JP8-Pad6)") (class "Default")
      (node (ref "JP8") (pin "6") (pinfunction "6_6") (pintype "passive"))
    )
    (net (code "88") (name "unconnected-(U$1-PadGND)") (class "Default")
      (node (ref "U$1") (pin "GND") (pinfunction "GND_GND") (pintype "power_in"))
    )
    (net (code "89") (name "unconnected-(U$1-PadVCC)") (class "Default")
      (node (ref "U$1") (pin "VCC") (pinfunction "VCC_VCC") (pintype "power_in"))
    )
    (net (code "90") (name "unconnected-(U$2-PadGND)") (class "Default")
      (node (ref "U$2") (pin "GND") (pinfunction "GND_GND") (pintype "power_in"))
    )
    (net (code "91") (name "unconnected-(U$2-PadVCC)") (class "Default")
      (node (ref "U$2") (pin "VCC") (pinfunction "VCC_VCC") (pintype "power_in"))
    )
    (net (code "92") (name "unconnected-(U$3-PadA0)") (class "Default")
      (node (ref "U$3") (pin "A0") (pinfunction "A0_A0") (pintype "bidirectional"))
    )
    (net (code "93") (name "unconnected-(U$3-PadCLK)") (class "Default")
      (node (ref "U$3") (pin "CLK") (pinfunction "CLK_CLK") (pintype "bidirectional"))
    )
    (net (code "94") (name "unconnected-(U$3-PadCMD)") (class "Default")
      (node (ref "U$3") (pin "CMD") (pinfunction "CMD_CMD") (pintype "bidirectional"))
    )
    (net (code "95") (name "unconnected-(U$3-PadD2)") (class "Default")
      (node (ref "U$3") (pin "D2") (pinfunction "D2_D2") (pintype "bidirectional"))
    )
    (net (code "96") (name "unconnected-(U$3-PadD3)") (class "Default")
      (node (ref "U$3") (pin "D3") (pinfunction "D3_D3") (pintype "bidirectional"))
    )
    (net (code "97") (name "unconnected-(U$3-PadD4)") (class "Default")
      (node (ref "U$3") (pin "D4") (pinfunction "D4_D4") (pintype "bidirectional"))
    )
    (net (code "98") (name "unconnected-(U$3-PadEN)") (class "Default")
      (node (ref "U$3") (pin "EN") (pinfunction "EN_EN") (pintype "bidirectional"))
    )
    (net (code "99") (name "unconnected-(U$3-PadRST)") (class "Default")
      (node (ref "U$3") (pin "RST") (pinfunction "RST_RST") (pintype "bidirectional"))
    )
    (net (code "100") (name "unconnected-(U$3-PadRSV)") (class "Default")
      (node (ref "U$3") (pin "RSV") (pinfunction "RSV_RSV") (pintype "bidirectional"))
    )
    (net (code "101") (name "unconnected-(U$3-PadRX)") (class "Default")
      (node (ref "U$3") (pin "RX") (pinfunction "RX_RX") (pintype "bidirectional"))
    )
    (net (code "102") (name "unconnected-(U$3-PadSD0)") (class "Default")
      (node (ref "U$3") (pin "SD0") (pinfunction "SD0_SD0") (pintype "bidirectional"))
    )
    (net (code "103") (name "unconnected-(U$3-PadSD1)") (class "Default")
      (node (ref "U$3") (pin "SD1") (pinfunction "SD1_SD1") (pintype "bidirectional"))
    )
    (net (code "104") (name "unconnected-(U$3-PadSD2)") (class "Default")
      (node (ref "U$3") (pin "SD2") (pinfunction "SD2_SD2") (pintype "bidirectional"))
    )
    (net (code "105") (name "unconnected-(U$3-PadSD3)") (class "Default")
      (node (ref "U$3") (pin "SD3") (pinfunction "SD3_SD3") (pintype "bidirectional"))
    )
    (net (code "106") (name "unconnected-(U$3-PadTX)") (class "Default")
      (node (ref "U$3") (pin "TX") (pinfunction "TX_TX") (pintype "bidirectional"))
    )
    (net (code "107") (name "unconnected-(U$3-RSV-PadRSV@1)") (class "Default")
      (node (ref "U$3") (pin "RSV@1") (pinfunction "RSV_RSV@1") (pintype "bidirectional"))
    )
    (net (code "108") (name "unconnected-(U$6-18:VSS-Pad18)") (class "Default")
      (node (ref "U$6") (pin "18") (pinfunction "18:VSS_18") (pintype "bidirectional"))
    )
    (net (code "109") (name "unconnected-(U$6-19:VDD-Pad19)") (class "Default")
      (node (ref "U$6") (pin "19") (pinfunction "19:VDD_19") (pintype "bidirectional"))
    )
    (net (code "110") (name "unconnected-(U$6-30:VCAP-Pad30)") (class "Default")
      (node (ref "U$6") (pin "30") (pinfunction "30:VCAP_30") (pintype "bidirectional"))
    )
    (net (code "111") (name "unconnected-(U$6-60:BOOT0-Pad60)") (class "Default")
      (node (ref "U$6") (pin "60") (pinfunction "60:BOOT0_60") (pintype "bidirectional"))
    )
    (net (code "112") (name "unconnected-(U$6-63:VSS-Pad63)") (class "Default")
      (node (ref "U$6") (pin "63") (pinfunction "63:VSS_63") (pintype "bidirectional"))
    )
    (net (code "113") (name "unconnected-(U$6-64:VDD-Pad64)") (class "Default")
      (node (ref "U$6") (pin "64") (pinfunction "64:VDD_64") (pintype "bidirectional"))
    )
    (net (code "114") (name "unconnected-(U$6-PB3-Pad55)") (class "Default")
      (node (ref "U$6") (pin "55") (pinfunction "PB3_55") (pintype "bidirectional"))
    )
    (net (code "115") (name "unconnected-(U$6-PC3-Pad11)") (class "Default")
      (node (ref "U$6") (pin "11") (pinfunction "PC3_11") (pintype "bidirectional"))
    )
    (net (code "116") (name "unconnected-(U$6-PC15-Pad4)") (class "Default")
      (node (ref "U$6") (pin "4") (pinfunction "PC15_4") (pintype "bidirectional"))
    )
    (net (code "117") (name "unconnected-(U$6-PH0-Pad5)") (class "Default")
      (node (ref "U$6") (pin "5") (pinfunction "PH0_5") (pintype "bidirectional"))
    )
    (net (code "118") (name "unconnected-(U$6-PH1-Pad6)") (class "Default")
      (node (ref "U$6") (pin "6") (pinfunction "PH1_6") (pintype "bidirectional"))
    )
    (net (code "119") (name "unconnected-(U$7-A2-Pad2)") (class "Default")
      (node (ref "U$7") (pin "2") (pinfunction "A2_2") (pintype "bidirectional"))
    )
    (net (code "120") (name "unconnected-(U$7-A3-Pad3)") (class "Default")
      (node (ref "U$7") (pin "3") (pinfunction "A3_3") (pintype "bidirectional"))
    )
    (net (code "121") (name "unconnected-(U$7-A5-Pad5)") (class "Default")
      (node (ref "U$7") (pin "5") (pinfunction "A5_5") (pintype "bidirectional"))
    )
    (net (code "122") (name "unconnected-(U$7-A6-Pad6)") (class "Default")
      (node (ref "U$7") (pin "6") (pinfunction "A6_6") (pintype "bidirectional"))
    )
    (net (code "123") (name "unconnected-(U$7-A7-Pad7)") (class "Default")
      (node (ref "U$7") (pin "7") (pinfunction "A7_7") (pintype "bidirectional"))
    )
    (net (code "124") (name "unconnected-(U$7-A8-Pad8)") (class "Default")
      (node (ref "U$7") (pin "8") (pinfunction "A8_8") (pintype "bidirectional"))
    )
    (net (code "125") (name "unconnected-(U$7-A10-Pad10)") (class "Default")
      (node (ref "U$7") (pin "10") (pinfunction "A10_10") (pintype "bidirectional"))
    )
    (net (code "126") (name "unconnected-(U$7-A11-Pad11)") (class "Default")
      (node (ref "U$7") (pin "11") (pinfunction "A11_11") (pintype "bidirectional"))
    )
    (net (code "127") (name "unconnected-(U$7-B2-Pad14)") (class "Default")
      (node (ref "U$7") (pin "14") (pinfunction "B2_14") (pintype "bidirectional"))
    )
    (net (code "128") (name "unconnected-(U$7-B3-Pad15)") (class "Default")
      (node (ref "U$7") (pin "15") (pinfunction "B3_15") (pintype "bidirectional"))
    )
    (net (code "129") (name "unconnected-(U$7-B5-Pad17)") (class "Default")
      (node (ref "U$7") (pin "17") (pinfunction "B5_17") (pintype "bidirectional"))
    )
    (net (code "130") (name "unconnected-(U$7-B6-Pad18)") (class "Default")
      (node (ref "U$7") (pin "18") (pinfunction "B6_18") (pintype "bidirectional"))
    )
    (net (code "131") (name "unconnected-(U$7-B7-Pad19)") (class "Default")
      (node (ref "U$7") (pin "19") (pinfunction "B7_19") (pintype "bidirectional"))
    )
    (net (code "132") (name "unconnected-(U$7-B8-Pad20)") (class "Default")
      (node (ref "U$7") (pin "20") (pinfunction "B8_20") (pintype "bidirectional"))
    )
    (net (code "133") (name "unconnected-(U$7-B10-Pad22)") (class "Default")
      (node (ref "U$7") (pin "22") (pinfunction "B10_22") (pintype "bidirectional"))
    )
    (net (code "134") (name "unconnected-(U$7-B11-Pad23)") (class "Default")
      (node (ref "U$7") (pin "23") (pinfunction "B11_23") (pintype "bidirectional"))
    )
    (net (code "135") (name "unconnected-(U$17-A2-Pad2)") (class "Default")
      (node (ref "U$17") (pin "2") (pinfunction "A2_2") (pintype "bidirectional"))
    )
    (net (code "136") (name "unconnected-(U$17-A3-Pad3)") (class "Default")
      (node (ref "U$17") (pin "3") (pinfunction "A3_3") (pintype "bidirectional"))
    )
    (net (code "137") (name "unconnected-(U$17-A5-Pad5)") (class "Default")
      (node (ref "U$17") (pin "5") (pinfunction "A5_5") (pintype "bidirectional"))
    )
    (net (code "138") (name "unconnected-(U$17-A6-Pad6)") (class "Default")
      (node (ref "U$17") (pin "6") (pinfunction "A6_6") (pintype "bidirectional"))
    )
    (net (code "139") (name "unconnected-(U$17-A7-Pad7)") (class "Default")
      (node (ref "U$17") (pin "7") (pinfunction "A7_7") (pintype "bidirectional"))
    )
    (net (code "140") (name "unconnected-(U$17-A8-Pad8)") (class "Default")
      (node (ref "U$17") (pin "8") (pinfunction "A8_8") (pintype "bidirectional"))
    )
    (net (code "141") (name "unconnected-(U$17-A10-Pad10)") (class "Default")
      (node (ref "U$17") (pin "10") (pinfunction "A10_10") (pintype "bidirectional"))
    )
    (net (code "142") (name "unconnected-(U$17-A11-Pad11)") (class "Default")
      (node (ref "U$17") (pin "11") (pinfunction "A11_11") (pintype "bidirectional"))
    )
    (net (code "143") (name "unconnected-(U$17-B2-Pad14)") (class "Default")
      (node (ref "U$17") (pin "14") (pinfunction "B2_14") (pintype "bidirectional"))
    )
    (net (code "144") (name "unconnected-(U$17-B3-Pad15)") (class "Default")
      (node (ref "U$17") (pin "15") (pinfunction "B3_15") (pintype "bidirectional"))
    )
    (net (code "145") (name "unconnected-(U$17-B5-Pad17)") (class "Default")
      (node (ref "U$17") (pin "17") (pinfunction "B5_17") (pintype "bidirectional"))
    )
    (net (code "146") (name "unconnected-(U$17-B6-Pad18)") (class "Default")
      (node (ref "U$17") (pin "18") (pinfunction "B6_18") (pintype "bidirectional"))
    )
    (net (code "147") (name "unconnected-(U$17-B7-Pad19)") (class "Default")
      (node (ref "U$17") (pin "19") (pinfunction "B7_19") (pintype "bidirectional"))
    )
    (net (code "148") (name "unconnected-(U$17-B8-Pad20)") (class "Default")
      (node (ref "U$17") (pin "20") (pinfunction "B8_20") (pintype "bidirectional"))
    )
    (net (code "149") (name "unconnected-(U$17-B10-Pad22)") (class "Default")
      (node (ref "U$17") (pin "22") (pinfunction "B10_22") (pintype "bidirectional"))
    )
    (net (code "150") (name "unconnected-(U$17-B11-Pad23)") (class "Default")
      (node (ref "U$17") (pin "23") (pinfunction "B11_23") (pintype "bidirectional"))
    )
    (net (code "151") (name "unconnected-(U$21-PadGND)") (class "Default")
      (node (ref "U$21") (pin "GND") (pinfunction "GND_GND") (pintype "power_in"))
    )
    (net (code "152") (name "unconnected-(U$21-PadVCC)") (class "Default")
      (node (ref "U$21") (pin "VCC") (pinfunction "VCC_VCC") (pintype "power_in"))
    )
    (net (code "153") (name "unconnected-(U$22-PadGND)") (class "Default")
      (node (ref "U$22") (pin "GND") (pinfunction "GND_GND") (pintype "power_in"))
    )
    (net (code "154") (name "unconnected-(U$22-PadVCC)") (class "Default")
      (node (ref "U$22") (pin "VCC") (pinfunction "VCC_VCC") (pintype "power_in"))
    )
    (net (code "155") (name "unconnected-(U$23-18:VSS-Pad18)") (class "Default")
      (node (ref "U$23") (pin "18") (pinfunction "18:VSS_18") (pintype "bidirectional"))
    )
    (net (code "156") (name "unconnected-(U$23-19:VDD-Pad19)") (class "Default")
      (node (ref "U$23") (pin "19") (pinfunction "19:VDD_19") (pintype "bidirectional"))
    )
    (net (code "157") (name "unconnected-(U$23-30:VCAP-Pad30)") (class "Default")
      (node (ref "U$23") (pin "30") (pinfunction "30:VCAP_30") (pintype "bidirectional"))
    )
    (net (code "158") (name "unconnected-(U$23-60:BOOT0-Pad60)") (class "Default")
      (node (ref "U$23") (pin "60") (pinfunction "60:BOOT0_60") (pintype "bidirectional"))
    )
    (net (code "159") (name "unconnected-(U$23-63:VSS-Pad63)") (class "Default")
      (node (ref "U$23") (pin "63") (pinfunction "63:VSS_63") (pintype "bidirectional"))
    )
    (net (code "160") (name "unconnected-(U$23-64:VDD-Pad64)") (class "Default")
      (node (ref "U$23") (pin "64") (pinfunction "64:VDD_64") (pintype "bidirectional"))
    )
    (net (code "161") (name "unconnected-(U$23-PB3-Pad55)") (class "Default")
      (node (ref "U$23") (pin "55") (pinfunction "PB3_55") (pintype "bidirectional"))
    )
    (net (code "162") (name "unconnected-(U$23-PC3-Pad11)") (class "Default")
      (node (ref "U$23") (pin "11") (pinfunction "PC3_11") (pintype "bidirectional"))
    )
    (net (code "163") (name "unconnected-(U$23-PC15-Pad4)") (class "Default")
      (node (ref "U$23") (pin "4") (pinfunction "PC15_4") (pintype "bidirectional"))
    )
    (net (code "164") (name "unconnected-(U$23-PH0-Pad5)") (class "Default")
      (node (ref "U$23") (pin "5") (pinfunction "PH0_5") (pintype "bidirectional"))
    )
    (net (code "165") (name "unconnected-(U$23-PH1-Pad6)") (class "Default")
      (node (ref "U$23") (pin "6") (pinfunction "PH1_6") (pintype "bidirectional"))
    )
    (net (code "166") (name "unconnected-(U$24-PadA0)") (class "Default")
      (node (ref "U$24") (pin "A0") (pinfunction "A0_A0") (pintype "bidirectional"))
    )
    (net (code "167") (name "unconnected-(U$24-PadCLK)") (class "Default")
      (node (ref "U$24") (pin "CLK") (pinfunction "CLK_CLK") (pintype "bidirectional"))
    )
    (net (code "168") (name "unconnected-(U$24-PadCMD)") (class "Default")
      (node (ref "U$24") (pin "CMD") (pinfunction "CMD_CMD") (pintype "bidirectional"))
    )
    (net (code "169") (name "unconnected-(U$24-PadD2)") (class "Default")
      (node (ref "U$24") (pin "D2") (pinfunction "D2_D2") (pintype "bidirectional"))
    )
    (net (code "170") (name "unconnected-(U$24-PadD3)") (class "Default")
      (node (ref "U$24") (pin "D3") (pinfunction "D3_D3") (pintype "bidirectional"))
    )
    (net (code "171") (name "unconnected-(U$24-PadD4)") (class "Default")
      (node (ref "U$24") (pin "D4") (pinfunction "D4_D4") (pintype "bidirectional"))
    )
    (net (code "172") (name "unconnected-(U$24-PadEN)") (class "Default")
      (node (ref "U$24") (pin "EN") (pinfunction "EN_EN") (pintype "bidirectional"))
    )
    (net (code "173") (name "unconnected-(U$24-PadRST)") (class "Default")
      (node (ref "U$24") (pin "RST") (pinfunction "RST_RST") (pintype "bidirectional"))
    )
    (net (code "174") (name "unconnected-(U$24-PadRSV)") (class "Default")
      (node (ref "U$24") (pin "RSV") (pinfunction "RSV_RSV") (pintype "bidirectional"))
    )
    (net (code "175") (name "unconnected-(U$24-PadRX)") (class "Default")
      (node (ref "U$24") (pin "RX") (pinfunction "RX_RX") (pintype "bidirectional"))
    )
    (net (code "176") (name "unconnected-(U$24-PadSD0)") (class "Default")
      (node (ref "U$24") (pin "SD0") (pinfunction "SD0_SD0") (pintype "bidirectional"))
    )
    (net (code "177") (name "unconnected-(U$24-PadSD1)") (class "Default")
      (node (ref "U$24") (pin "SD1") (pinfunction "SD1_SD1") (pintype "bidirectional"))
    )
    (net (code "178") (name "unconnected-(U$24-PadSD2)") (class "Default")
      (node (ref "U$24") (pin "SD2") (pinfunction "SD2_SD2") (pintype "bidirectional"))
    )
    (net (code "179") (name "unconnected-(U$24-PadSD3)") (class "Default")
      (node (ref "U$24") (pin "SD3") (pinfunction "SD3_SD3") (pintype "bidirectional"))
    )
    (net (code "180") (name "unconnected-(U$24-PadTX)") (class "Default")
      (node (ref "U$24") (pin "TX") (pinfunction "TX_TX") (pintype "bidirectional"))
    )
    (net (code "181") (name "unconnected-(U$24-RSV-PadRSV@1)") (class "Default")
      (node (ref "U$24") (pin "RSV@1") (pinfunction "RSV_RSV@1") (pintype "bidirectional"))
    )
  )
)
